# LLC_v2.net
KiCad netlist of a schematic drawn in EAGLE
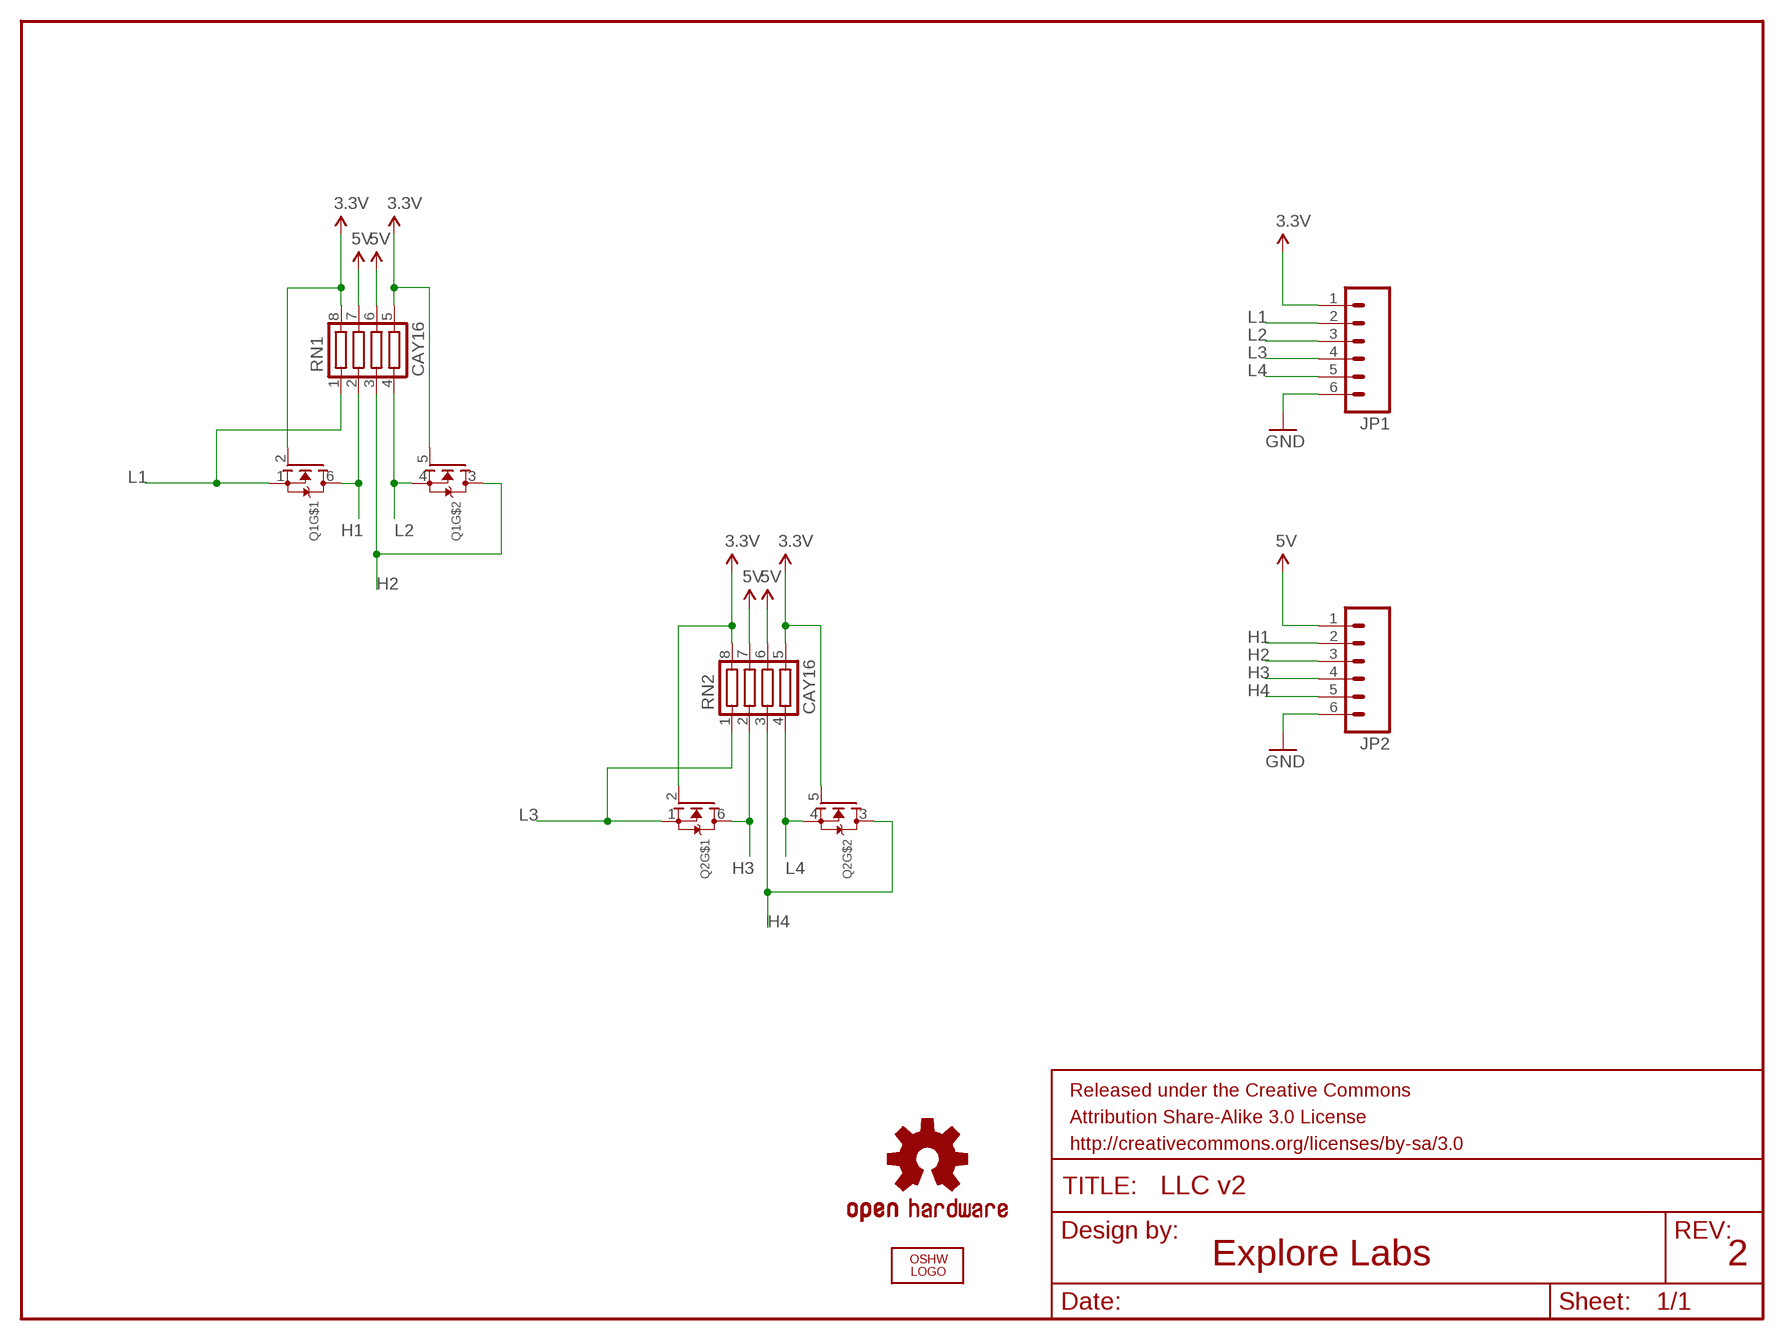
[diagram p0: schematic, sheet 1]

(export (version "E")
  (design (tool "Eeschema 10.0.6"))
  (components
    (comp (ref "JP1")
      (value "M06SIP")
      (footprint "eagle-import:1X06")
      (libsource (lib "eagle-import") (part "M06SIP"))
    )
    (comp (ref "JP2")
      (value "M06SIP")
      (footprint "eagle-import:1X06")
      (libsource (lib "eagle-import") (part "M06SIP"))
    )
    (comp (ref "LOGO1")
      (value "OSHW_LOGO_FILLX0100-NT")
      (footprint "eagle-import:OSHW_FILLX100_NOTEXT")
      (libsource (lib "eagle-import") (part "OSHW_LOGO_FILLX0100-NT"))
    )
    (comp (ref "Q1")
      (value "MOSFET-N_DUAL")
      (footprint "eagle-import:SOT363")
      (libsource (lib "eagle-import") (part "MOSFET-N_DUAL"))
    )
    (comp (ref "Q2")
      (value "MOSFET-N_DUAL")
      (footprint "eagle-import:SOT363")
      (libsource (lib "eagle-import") (part "MOSFET-N_DUAL"))
    )
    (comp (ref "RN1")
      (value "CAY16")
      (footprint "eagle-import:CTS742C083")
      (libsource (lib "eagle-import") (part "CAY16"))
    )
    (comp (ref "RN2")
      (value "CAY16")
      (footprint "eagle-import:CTS742C083")
      (libsource (lib "eagle-import") (part "CAY16"))
    )
    (comp (ref "U$6")
      (value "OSHW-LOGOS")
      (footprint "eagle-import:OSHW-LOGO-S")
      (libsource (lib "eagle-import") (part "OSHW-LOGOS"))
    )
  )
  (nets
    (net (code "1") (name "/H1") (class "Default")
      (node (ref "JP2") (pin "2") (pinfunction "2_2") (pintype "passive"))
      (node (ref "Q1") (pin "6") (pinfunction "D_6") (pintype "bidirectional"))
      (node (ref "RN1") (pin "2") (pinfunction "2_2") (pintype "passive"))
    )
    (net (code "2") (name "/H2") (class "Default")
      (node (ref "JP2") (pin "3") (pinfunction "3_3") (pintype "passive"))
      (node (ref "Q1") (pin "3") (pinfunction "D_3") (pintype "bidirectional"))
      (node (ref "RN1") (pin "3") (pinfunction "3_3") (pintype "passive"))
    )
    (net (code "3") (name "/H3") (class "Default")
      (node (ref "JP2") (pin "4") (pinfunction "4_4") (pintype "passive"))
      (node (ref "Q2") (pin "6") (pinfunction "D_6") (pintype "bidirectional"))
      (node (ref "RN2") (pin "2") (pinfunction "2_2") (pintype "passive"))
    )
    (net (code "4") (name "/H4") (class "Default")
      (node (ref "JP2") (pin "5") (pinfunction "5_5") (pintype "passive"))
      (node (ref "Q2") (pin "3") (pinfunction "D_3") (pintype "bidirectional"))
      (node (ref "RN2") (pin "3") (pinfunction "3_3") (pintype "passive"))
    )
    (net (code "5") (name "/L1") (class "Default")
      (node (ref "JP1") (pin "2") (pinfunction "2_2") (pintype "passive"))
      (node (ref "Q1") (pin "1") (pinfunction "S_1") (pintype "bidirectional"))
      (node (ref "RN1") (pin "1") (pinfunction "1_1") (pintype "passive"))
    )
    (net (code "6") (name "/L2") (class "Default")
      (node (ref "JP1") (pin "3") (pinfunction "3_3") (pintype "passive"))
      (node (ref "Q1") (pin "4") (pinfunction "S_4") (pintype "bidirectional"))
      (node (ref "RN1") (pin "4") (pinfunction "4_4") (pintype "passive"))
    )
    (net (code "7") (name "/L3") (class "Default")
      (node (ref "JP1") (pin "4") (pinfunction "4_4") (pintype "passive"))
      (node (ref "Q2") (pin "1") (pinfunction "S_1") (pintype "bidirectional"))
      (node (ref "RN2") (pin "1") (pinfunction "1_1") (pintype "passive"))
    )
    (net (code "8") (name "/L4") (class "Default")
      (node (ref "JP1") (pin "5") (pinfunction "5_5") (pintype "passive"))
      (node (ref "Q2") (pin "4") (pinfunction "S_4") (pintype "bidirectional"))
      (node (ref "RN2") (pin "4") (pinfunction "4_4") (pintype "passive"))
    )
    (net (code "9") (name "3.3V") (class "Default")
      (node (ref "JP1") (pin "1") (pinfunction "1_1") (pintype "passive"))
      (node (ref "Q1") (pin "2") (pinfunction "G_2") (pintype "bidirectional"))
      (node (ref "Q1") (pin "5") (pinfunction "G_5") (pintype "bidirectional"))
      (node (ref "Q2") (pin "2") (pinfunction "G_2") (pintype "bidirectional"))
      (node (ref "Q2") (pin "5") (pinfunction "G_5") (pintype "bidirectional"))
      (node (ref "RN1") (pin "5") (pinfunction "5_5") (pintype "passive"))
      (node (ref "RN1") (pin "8") (pinfunction "8_8") (pintype "passive"))
      (node (ref "RN2") (pin "5") (pinfunction "5_5") (pintype "passive"))
      (node (ref "RN2") (pin "8") (pinfunction "8_8") (pintype "passive"))
    )
    (net (code "10") (name "5V") (class "Default")
      (node (ref "JP2") (pin "1") (pinfunction "1_1") (pintype "passive"))
      (node (ref "RN1") (pin "6") (pinfunction "6_6") (pintype "passive"))
      (node (ref "RN1") (pin "7") (pinfunction "7_7") (pintype "passive"))
      (node (ref "RN2") (pin "6") (pinfunction "6_6") (pintype "passive"))
      (node (ref "RN2") (pin "7") (pinfunction "7_7") (pintype "passive"))
    )
    (net (code "11") (name "GND") (class "Default")
      (node (ref "JP1") (pin "6") (pinfunction "6_6") (pintype "passive"))
      (node (ref "JP2") (pin "6") (pinfunction "6_6") (pintype "passive"))
    )
  )
)
